# NanjaTown.net
KiCad netlist of a schematic drawn in EAGLE
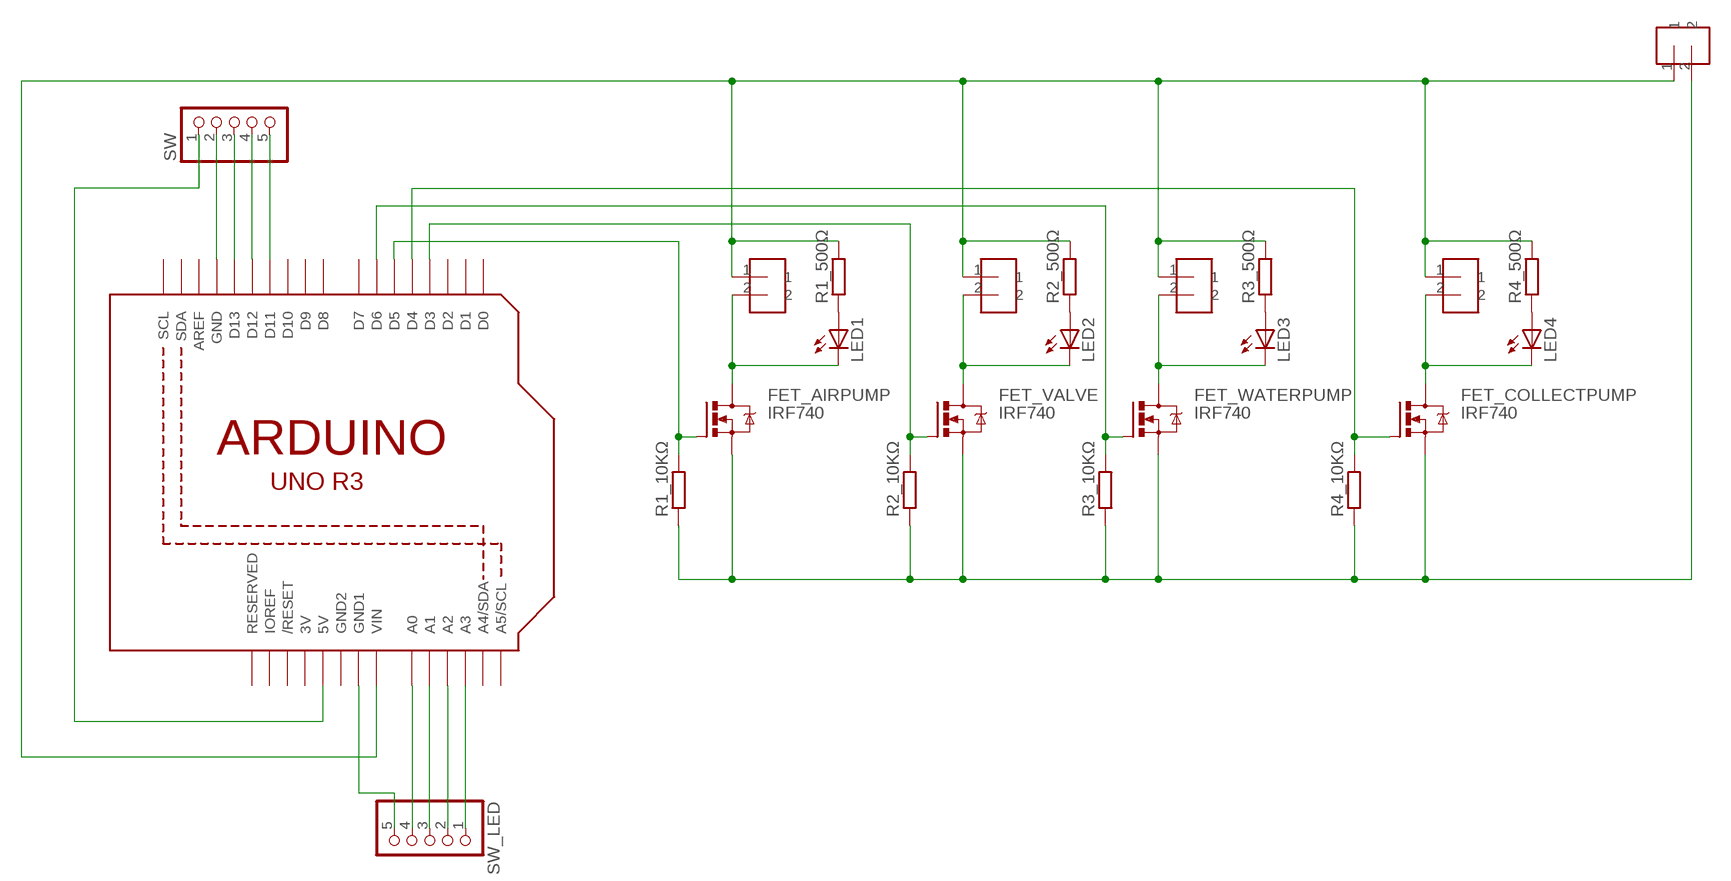
[diagram p0: schematic, sheet 1]

(export (version "E")
  (design (tool "Eeschema 10.0.6"))
  (components
    (comp (ref "FET_AIRPUMP")
      (value "IRF740")
      (footprint "eagle-import:TO220BV")
      (libsource (lib "eagle-import") (part "IRF740"))
    )
    (comp (ref "FET_COLLECTPUMP")
      (value "IRF740")
      (footprint "eagle-import:TO220BV")
      (libsource (lib "eagle-import") (part "IRF740"))
    )
    (comp (ref "FET_VALVE")
      (value "IRF740")
      (footprint "eagle-import:TO220BV")
      (libsource (lib "eagle-import") (part "IRF740"))
    )
    (comp (ref "FET_WATERPUMP")
      (value "IRF740")
      (footprint "eagle-import:TO220BV")
      (libsource (lib "eagle-import") (part "IRF740"))
    )
    (comp (ref "LED1")
      (value "LEDB156")
      (footprint "eagle-import:Q62902-B156")
      (libsource (lib "eagle-import") (part "LEDB156"))
    )
    (comp (ref "LED2")
      (value "LEDB156")
      (footprint "eagle-import:Q62902-B156")
      (libsource (lib "eagle-import") (part "LEDB156"))
    )
    (comp (ref "LED3")
      (value "LEDB156")
      (footprint "eagle-import:Q62902-B156")
      (libsource (lib "eagle-import") (part "LEDB156"))
    )
    (comp (ref "LED4")
      (value "LEDB156")
      (footprint "eagle-import:Q62902-B156")
      (libsource (lib "eagle-import") (part "LEDB156"))
    )
    (comp (ref "R1_10KΩ")
      (value "R-EU_0207/10")
      (footprint "eagle-import:0207_10")
      (libsource (lib "eagle-import") (part "R-EU_0207/10"))
    )
    (comp (ref "R1_500Ω")
      (value "R-EU_0207/10")
      (footprint "eagle-import:0207_10")
      (libsource (lib "eagle-import") (part "R-EU_0207/10"))
    )
    (comp (ref "R2_10KΩ")
      (value "R-EU_0207/10")
      (footprint "eagle-import:0207_10")
      (libsource (lib "eagle-import") (part "R-EU_0207/10"))
    )
    (comp (ref "R2_500Ω")
      (value "R-EU_0207/10")
      (footprint "eagle-import:0207_10")
      (libsource (lib "eagle-import") (part "R-EU_0207/10"))
    )
    (comp (ref "R3_10KΩ")
      (value "R-EU_0207/10")
      (footprint "eagle-import:0207_10")
      (libsource (lib "eagle-import") (part "R-EU_0207/10"))
    )
    (comp (ref "R3_500Ω")
      (value "R-EU_0207/10")
      (footprint "eagle-import:0207_10")
      (libsource (lib "eagle-import") (part "R-EU_0207/10"))
    )
    (comp (ref "R4_10KΩ")
      (value "R-EU_0207/10")
      (footprint "eagle-import:0207_10")
      (libsource (lib "eagle-import") (part "R-EU_0207/10"))
    )
    (comp (ref "R4_500Ω")
      (value "R-EU_0207/10")
      (footprint "eagle-import:0207_10")
      (libsource (lib "eagle-import") (part "R-EU_0207/10"))
    )
    (comp (ref "SW")
      (value "PINHD-1X5")
      (footprint "eagle-import:1X05")
      (libsource (lib "eagle-import") (part "PINHD-1X5"))
    )
    (comp (ref "SW_LED")
      (value "PINHD-1X5/90")
      (footprint "eagle-import:1X05_90")
      (libsource (lib "eagle-import") (part "PINHD-1X5/90"))
    )
    (comp (ref "TERMINAL_AIRPUMP")
      (value "TERMINAL_BLOCK_5.08MM")
      (footprint "eagle-import:TERMINAL_BLOCK_5.8MM")
      (libsource (lib "eagle-import") (part "TERMINAL_BLOCK_5.08MM"))
    )
    (comp (ref "TERMINAL_COLLECTPUMP")
      (value "TERMINAL_BLOCK_5.08MM")
      (footprint "eagle-import:TERMINAL_BLOCK_5.8MM")
      (libsource (lib "eagle-import") (part "TERMINAL_BLOCK_5.08MM"))
    )
    (comp (ref "TERMINAL_VALVE")
      (value "TERMINAL_BLOCK_5.08MM")
      (footprint "eagle-import:TERMINAL_BLOCK_5.8MM")
      (libsource (lib "eagle-import") (part "TERMINAL_BLOCK_5.08MM"))
    )
    (comp (ref "TERMINAL_WATERPUMP")
      (value "TERMINAL_BLOCK_5.08MM")
      (footprint "eagle-import:TERMINAL_BLOCK_5.8MM")
      (libsource (lib "eagle-import") (part "TERMINAL_BLOCK_5.08MM"))
    )
    (comp (ref "U1")
      (value "ARDUINOR3-DIMENSION")
      (footprint "eagle-import:ARDUINOR3")
      (libsource (lib "eagle-import") (part "ARDUINOR3-DIMENSION"))
    )
    (comp (ref "VCC_12V")
      (value "TERMINAL_BLOCK_5.08MM")
      (footprint "eagle-import:TERMINAL_BLOCK_5.8MM")
      (libsource (lib "eagle-import") (part "TERMINAL_BLOCK_5.08MM"))
    )
  )
  (nets
    (net (code "1") (name "/3V") (class "Default")
      (node (ref "U1") (pin "3V") (pinfunction "3V_3V") (pintype "power_in"))
    )
    (net (code "2") (name "/GND2") (class "Default")
      (node (ref "U1") (pin "GND2") (pinfunction "GND2_GND2") (pintype "power_in"))
    )
    (net (code "3") (name "Net-(FET_AIRPUMP-PadG)") (class "Default")
      (node (ref "FET_AIRPUMP") (pin "G") (pinfunction "G_G") (pintype "passive"))
      (node (ref "R1_10KΩ") (pin "2") (pinfunction "2_2") (pintype "passive"))
      (node (ref "U1") (pin "D5") (pinfunction "D5_D5") (pintype "bidirectional"))
    )
    (net (code "4") (name "Net-(FET_AIRPUMP-PadS)") (class "Default")
      (node (ref "FET_AIRPUMP") (pin "S") (pinfunction "S_S") (pintype "passive"))
      (node (ref "FET_COLLECTPUMP") (pin "S") (pinfunction "S_S") (pintype "passive"))
      (node (ref "FET_VALVE") (pin "S") (pinfunction "S_S") (pintype "passive"))
      (node (ref "FET_WATERPUMP") (pin "S") (pinfunction "S_S") (pintype "passive"))
      (node (ref "R1_10KΩ") (pin "1") (pinfunction "1_1") (pintype "passive"))
      (node (ref "R2_10KΩ") (pin "1") (pinfunction "1_1") (pintype "passive"))
      (node (ref "R3_10KΩ") (pin "1") (pinfunction "1_1") (pintype "passive"))
      (node (ref "R4_10KΩ") (pin "1") (pinfunction "1_1") (pintype "passive"))
      (node (ref "VCC_12V") (pin "2") (pinfunction "2_2") (pintype "bidirectional"))
    )
    (net (code "5") (name "Net-(FET_COLLECTPUMP-PadG)") (class "Default")
      (node (ref "FET_COLLECTPUMP") (pin "G") (pinfunction "G_G") (pintype "passive"))
      (node (ref "R4_10KΩ") (pin "2") (pinfunction "2_2") (pintype "passive"))
      (node (ref "U1") (pin "D4") (pinfunction "D4_D4") (pintype "bidirectional"))
    )
    (net (code "6") (name "Net-(FET_VALVE-PadG)") (class "Default")
      (node (ref "FET_VALVE") (pin "G") (pinfunction "G_G") (pintype "passive"))
      (node (ref "R2_10KΩ") (pin "2") (pinfunction "2_2") (pintype "passive"))
      (node (ref "U1") (pin "D3") (pinfunction "D3_D3") (pintype "bidirectional"))
    )
    (net (code "7") (name "Net-(FET_WATERPUMP-PadG)") (class "Default")
      (node (ref "FET_WATERPUMP") (pin "G") (pinfunction "G_G") (pintype "passive"))
      (node (ref "R3_10KΩ") (pin "2") (pinfunction "2_2") (pintype "passive"))
      (node (ref "U1") (pin "D6") (pinfunction "D6_D6") (pintype "bidirectional"))
    )
    (net (code "8") (name "Net-(LED1-C)") (class "Default")
      (node (ref "FET_AIRPUMP") (pin "D") (pinfunction "D_D") (pintype "passive"))
      (node (ref "LED1") (pin "K") (pinfunction "C_K") (pintype "passive"))
      (node (ref "TERMINAL_AIRPUMP") (pin "2") (pinfunction "2_2") (pintype "bidirectional"))
    )
    (net (code "9") (name "Net-(LED1-PadA)") (class "Default")
      (node (ref "LED1") (pin "A") (pinfunction "A_A") (pintype "passive"))
      (node (ref "R1_500Ω") (pin "1") (pinfunction "1_1") (pintype "passive"))
    )
    (net (code "10") (name "Net-(LED2-C)") (class "Default")
      (node (ref "FET_VALVE") (pin "D") (pinfunction "D_D") (pintype "passive"))
      (node (ref "LED2") (pin "K") (pinfunction "C_K") (pintype "passive"))
      (node (ref "TERMINAL_VALVE") (pin "2") (pinfunction "2_2") (pintype "bidirectional"))
    )
    (net (code "11") (name "Net-(LED2-PadA)") (class "Default")
      (node (ref "LED2") (pin "A") (pinfunction "A_A") (pintype "passive"))
      (node (ref "R2_500Ω") (pin "1") (pinfunction "1_1") (pintype "passive"))
    )
    (net (code "12") (name "Net-(LED3-C)") (class "Default")
      (node (ref "FET_WATERPUMP") (pin "D") (pinfunction "D_D") (pintype "passive"))
      (node (ref "LED3") (pin "K") (pinfunction "C_K") (pintype "passive"))
      (node (ref "TERMINAL_WATERPUMP") (pin "2") (pinfunction "2_2") (pintype "bidirectional"))
    )
    (net (code "13") (name "Net-(LED3-PadA)") (class "Default")
      (node (ref "LED3") (pin "A") (pinfunction "A_A") (pintype "passive"))
      (node (ref "R3_500Ω") (pin "1") (pinfunction "1_1") (pintype "passive"))
    )
    (net (code "14") (name "Net-(LED4-C)") (class "Default")
      (node (ref "FET_COLLECTPUMP") (pin "D") (pinfunction "D_D") (pintype "passive"))
      (node (ref "LED4") (pin "K") (pinfunction "C_K") (pintype "passive"))
      (node (ref "TERMINAL_COLLECTPUMP") (pin "2") (pinfunction "2_2") (pintype "bidirectional"))
    )
    (net (code "15") (name "Net-(LED4-PadA)") (class "Default")
      (node (ref "LED4") (pin "A") (pinfunction "A_A") (pintype "passive"))
      (node (ref "R4_500Ω") (pin "1") (pinfunction "1_1") (pintype "passive"))
    )
    (net (code "16") (name "Net-(R1_500Ω-Pad2)") (class "Default")
      (node (ref "R1_500Ω") (pin "2") (pinfunction "2_2") (pintype "passive"))
      (node (ref "R2_500Ω") (pin "2") (pinfunction "2_2") (pintype "passive"))
      (node (ref "R3_500Ω") (pin "2") (pinfunction "2_2") (pintype "passive"))
      (node (ref "R4_500Ω") (pin "2") (pinfunction "2_2") (pintype "passive"))
      (node (ref "TERMINAL_AIRPUMP") (pin "1") (pinfunction "1_1") (pintype "bidirectional"))
      (node (ref "TERMINAL_COLLECTPUMP") (pin "1") (pinfunction "1_1") (pintype "bidirectional"))
      (node (ref "TERMINAL_VALVE") (pin "1") (pinfunction "1_1") (pintype "bidirectional"))
      (node (ref "TERMINAL_WATERPUMP") (pin "1") (pinfunction "1_1") (pintype "bidirectional"))
      (node (ref "U1") (pin "VIN") (pinfunction "VIN_VIN") (pintype "power_in"))
      (node (ref "VCC_12V") (pin "1") (pinfunction "1_1") (pintype "bidirectional"))
    )
    (net (code "17") (name "Net-(SW-Pad1)") (class "Default")
      (node (ref "SW") (pin "1") (pinfunction "1_1") (pintype "passive"))
      (node (ref "U1") (pin "5V") (pinfunction "5V_5V") (pintype "power_in"))
    )
    (net (code "18") (name "Net-(SW-Pad2)") (class "Default")
      (node (ref "SW") (pin "2") (pinfunction "2_2") (pintype "passive"))
      (node (ref "U1") (pin "GND") (pinfunction "GND_GND") (pintype "power_in"))
    )
    (net (code "19") (name "Net-(SW-Pad3)") (class "Default")
      (node (ref "SW") (pin "3") (pinfunction "3_3") (pintype "passive"))
      (node (ref "U1") (pin "D13") (pinfunction "D13_D13") (pintype "bidirectional"))
    )
    (net (code "20") (name "Net-(SW-Pad4)") (class "Default")
      (node (ref "SW") (pin "4") (pinfunction "4_4") (pintype "passive"))
      (node (ref "U1") (pin "D12") (pinfunction "D12_D12") (pintype "bidirectional"))
    )
    (net (code "21") (name "Net-(SW-Pad5)") (class "Default")
      (node (ref "SW") (pin "5") (pinfunction "5_5") (pintype "passive"))
      (node (ref "U1") (pin "D11") (pinfunction "D11_D11") (pintype "bidirectional"))
    )
    (net (code "22") (name "Net-(SW_LED-Pad1)") (class "Default")
      (node (ref "SW_LED") (pin "1") (pinfunction "1_1") (pintype "passive"))
      (node (ref "U1") (pin "A3") (pinfunction "A3_A3") (pintype "bidirectional"))
    )
    (net (code "23") (name "Net-(SW_LED-Pad2)") (class "Default")
      (node (ref "SW_LED") (pin "2") (pinfunction "2_2") (pintype "passive"))
      (node (ref "U1") (pin "A2") (pinfunction "A2_A2") (pintype "bidirectional"))
    )
    (net (code "24") (name "Net-(SW_LED-Pad3)") (class "Default")
      (node (ref "SW_LED") (pin "3") (pinfunction "3_3") (pintype "passive"))
      (node (ref "U1") (pin "A1") (pinfunction "A1_A1") (pintype "bidirectional"))
    )
    (net (code "25") (name "Net-(SW_LED-Pad4)") (class "Default")
      (node (ref "SW_LED") (pin "4") (pinfunction "4_4") (pintype "passive"))
      (node (ref "U1") (pin "A0") (pinfunction "A0_A0") (pintype "bidirectional"))
    )
    (net (code "26") (name "Net-(SW_LED-Pad5)") (class "Default")
      (node (ref "SW_LED") (pin "5") (pinfunction "5_5") (pintype "passive"))
      (node (ref "U1") (pin "GND1") (pinfunction "GND1_GND1") (pintype "power_in"))
    )
    (net (code "27") (name "unconnected-(U1-A4{slash}SDA-PadA4)") (class "Default")
      (node (ref "U1") (pin "A4") (pinfunction "A4/SDA_A4") (pintype "bidirectional"))
    )
    (net (code "28") (name "unconnected-(U1-A5{slash}SCL-PadA5)") (class "Default")
      (node (ref "U1") (pin "A5") (pinfunction "A5/SCL_A5") (pintype "bidirectional"))
    )
    (net (code "29") (name "unconnected-(U1-PadAREF)") (class "Default")
      (node (ref "U1") (pin "AREF") (pinfunction "AREF_AREF") (pintype "bidirectional"))
    )
    (net (code "30") (name "unconnected-(U1-PadD0)") (class "Default")
      (node (ref "U1") (pin "D0") (pinfunction "D0_D0") (pintype "bidirectional"))
    )
    (net (code "31") (name "unconnected-(U1-PadD1)") (class "Default")
      (node (ref "U1") (pin "D1") (pinfunction "D1_D1") (pintype "bidirectional"))
    )
    (net (code "32") (name "unconnected-(U1-PadD2)") (class "Default")
      (node (ref "U1") (pin "D2") (pinfunction "D2_D2") (pintype "bidirectional"))
    )
    (net (code "33") (name "unconnected-(U1-PadD7)") (class "Default")
      (node (ref "U1") (pin "D7") (pinfunction "D7_D7") (pintype "bidirectional"))
    )
    (net (code "34") (name "unconnected-(U1-PadD8)") (class "Default")
      (node (ref "U1") (pin "D8") (pinfunction "D8_D8") (pintype "bidirectional"))
    )
    (net (code "35") (name "unconnected-(U1-PadD9)") (class "Default")
      (node (ref "U1") (pin "D9") (pinfunction "D9_D9") (pintype "bidirectional"))
    )
    (net (code "36") (name "unconnected-(U1-PadD10)") (class "Default")
      (node (ref "U1") (pin "D10") (pinfunction "D10_D10") (pintype "bidirectional"))
    )
    (net (code "37") (name "unconnected-(U1-PadIOREF)") (class "Default")
      (node (ref "U1") (pin "IOREF") (pinfunction "IOREF_IOREF") (pintype "output"))
    )
    (net (code "38") (name "unconnected-(U1-PadRESERVED)") (class "Default")
      (node (ref "U1") (pin "RESERVED") (pinfunction "RESERVED_RESERVED") (pintype "no_connect"))
    )
    (net (code "39") (name "unconnected-(U1-PadSCL)") (class "Default")
      (node (ref "U1") (pin "SCL") (pinfunction "SCL_SCL") (pintype "bidirectional"))
    )
    (net (code "40") (name "unconnected-(U1-PadSDA)") (class "Default")
      (node (ref "U1") (pin "SDA") (pinfunction "SDA_SDA") (pintype "bidirectional"))
    )
    (net (code "41") (name "unconnected-(U1-{slash}RESET-PadRESET)") (class "Default")
      (node (ref "U1") (pin "RESET") (pinfunction "/RESET_RESET") (pintype "bidirectional"))
    )
  )
)
